# Breadboard_Supply_5V.net
KiCad netlist of a schematic drawn in EAGLE
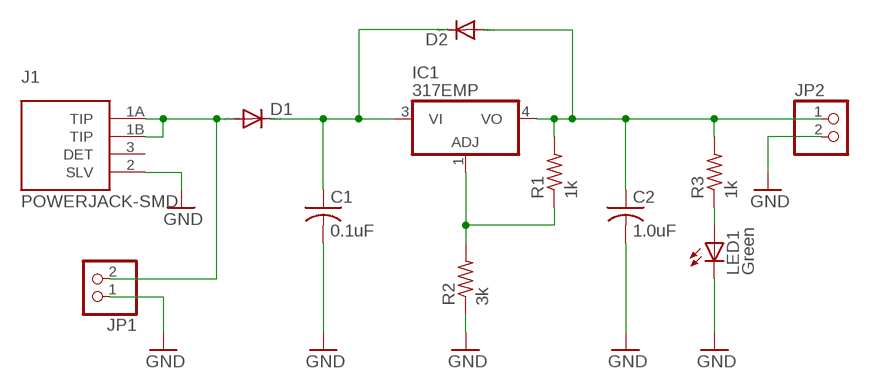
[diagram p0: schematic, sheet 1]

(export (version "E")
  (design (tool "Eeschema 10.0.6"))
  (components
    (comp (ref "C1")
      (value "0.1uF")
      (footprint "eagle-import:C0805")
      (libsource (lib "eagle-import") (part "C-USC0805"))
    )
    (comp (ref "C2")
      (value "1.0uF")
      (footprint "eagle-import:C0805")
      (libsource (lib "eagle-import") (part "C-USC0805"))
    )
    (comp (ref "D1")
      (value "DIODE-SMB")
      (footprint "eagle-import:SMB")
      (libsource (lib "eagle-import") (part "DIODE-SMB"))
    )
    (comp (ref "D2")
      (value "DIODE-SMB")
      (footprint "eagle-import:SMB")
      (libsource (lib "eagle-import") (part "DIODE-SMB"))
    )
    (comp (ref "IC1")
      (value "317EMP")
      (footprint "eagle-import:SOT223")
      (libsource (lib "eagle-import") (part "317EMP"))
    )
    (comp (ref "J1")
      (value "POWERJACK-SMD")
      (footprint "eagle-import:PJ-002AH-SMT")
      (libsource (lib "eagle-import") (part "POWERJACK-SMD"))
    )
    (comp (ref "JP1")
      (value "PINHD-1X2")
      (footprint "eagle-import:1X02")
      (libsource (lib "eagle-import") (part "PINHD-1X2"))
    )
    (comp (ref "JP2")
      (value "PINHD-1X2")
      (footprint "eagle-import:1X02")
      (libsource (lib "eagle-import") (part "PINHD-1X2"))
    )
    (comp (ref "LED1")
      (value "Green")
      (footprint "eagle-import:CHIPLED_0805")
      (libsource (lib "eagle-import") (part "LEDCHIPLED_0805"))
    )
    (comp (ref "R1")
      (value "1k")
      (footprint "eagle-import:R0805")
      (libsource (lib "eagle-import") (part "R-US_R0805"))
    )
    (comp (ref "R2")
      (value "3k")
      (footprint "eagle-import:R0805")
      (libsource (lib "eagle-import") (part "R-US_R0805"))
    )
    (comp (ref "R3")
      (value "1k")
      (footprint "eagle-import:R0805")
      (libsource (lib "eagle-import") (part "R-US_R0805"))
    )
  )
  (nets
    (net (code "1") (name "GND") (class "Default")
      (node (ref "C1") (pin "2") (pinfunction "2_2") (pintype "passive"))
      (node (ref "C2") (pin "2") (pinfunction "2_2") (pintype "passive"))
      (node (ref "J1") (pin "2") (pinfunction "SLV_2") (pintype "bidirectional"))
      (node (ref "JP1") (pin "1") (pinfunction "1_1") (pintype "passive"))
      (node (ref "JP2") (pin "2") (pinfunction "2_2") (pintype "passive"))
      (node (ref "LED1") (pin "C") (pinfunction "C_C") (pintype "passive"))
      (node (ref "R2") (pin "1") (pinfunction "1_1") (pintype "passive"))
    )
    (net (code "2") (name "Net-(D1-PadA)") (class "Default")
      (node (ref "D1") (pin "A") (pinfunction "A_A") (pintype "passive"))
      (node (ref "J1") (pin "1A") (pinfunction "TIP_1A") (pintype "bidirectional"))
      (node (ref "J1") (pin "1B") (pinfunction "TIP_1B") (pintype "bidirectional"))
      (node (ref "JP1") (pin "2") (pinfunction "2_2") (pintype "passive"))
    )
    (net (code "3") (name "Net-(IC1-ADJ)") (class "Default")
      (node (ref "IC1") (pin "1") (pinfunction "ADJ_1") (pintype "input"))
      (node (ref "R1") (pin "1") (pinfunction "1_1") (pintype "passive"))
      (node (ref "R2") (pin "2") (pinfunction "2_2") (pintype "passive"))
    )
    (net (code "4") (name "Net-(IC1-VI)") (class "Default")
      (node (ref "C1") (pin "1") (pinfunction "1_1") (pintype "passive"))
      (node (ref "D1") (pin "C") (pinfunction "C_C") (pintype "passive"))
      (node (ref "D2") (pin "C") (pinfunction "C_C") (pintype "passive"))
      (node (ref "IC1") (pin "3") (pinfunction "VI_3") (pintype "input"))
    )
    (net (code "5") (name "Net-(IC1-VO)") (class "Default")
      (node (ref "C2") (pin "1") (pinfunction "1_1") (pintype "passive"))
      (node (ref "D2") (pin "A") (pinfunction "A_A") (pintype "passive"))
      (node (ref "IC1") (pin "4") (pinfunction "VO_4") (pintype "passive"))
      (node (ref "JP2") (pin "1") (pinfunction "1_1") (pintype "passive"))
      (node (ref "R1") (pin "2") (pinfunction "2_2") (pintype "passive"))
      (node (ref "R3") (pin "2") (pinfunction "2_2") (pintype "passive"))
    )
    (net (code "6") (name "Net-(LED1-PadA)") (class "Default")
      (node (ref "LED1") (pin "A") (pinfunction "A_A") (pintype "passive"))
      (node (ref "R3") (pin "1") (pinfunction "1_1") (pintype "passive"))
    )
    (net (code "7") (name "unconnected-(J1-DET-Pad3)") (class "Default")
      (node (ref "J1") (pin "3") (pinfunction "DET_3") (pintype "bidirectional"))
    )
  )
)
